# PowerCastel.net
KiCad netlist of a schematic drawn in EAGLE
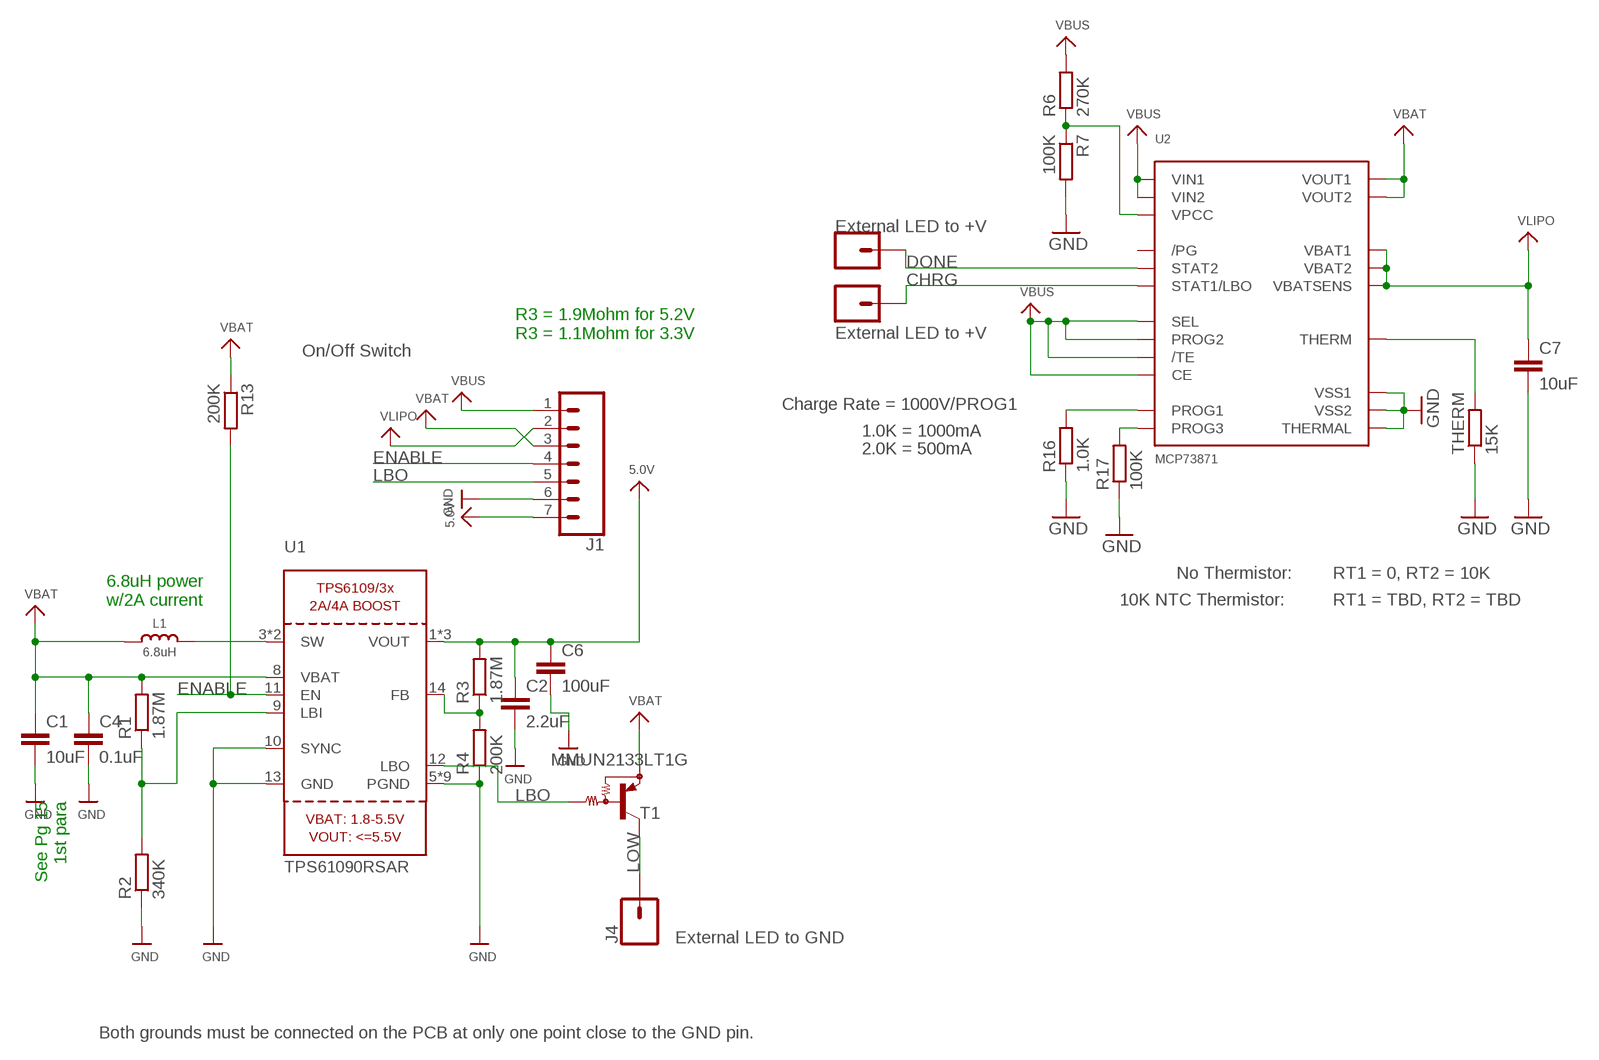
[diagram p0: schematic, sheet 1]

(export (version "E")
  (design (tool "Eeschema 10.0.6"))
  (components
    (comp (ref "C1")
      (value "10uF")
      (footprint "eagle-import:C0603")
      (libsource (lib "eagle-import") (part "C-EUC0603"))
    )
    (comp (ref "C2")
      (value "2.2uF")
      (footprint "eagle-import:C0603")
      (libsource (lib "eagle-import") (part "C-EUC0603"))
    )
    (comp (ref "C4")
      (value "0.1uF")
      (footprint "eagle-import:C0603")
      (libsource (lib "eagle-import") (part "C-EUC0603"))
    )
    (comp (ref "C6")
      (value "100uF")
      (footprint "eagle-import:C0805")
      (libsource (lib "eagle-import") (part "C-EUC0805"))
    )
    (comp (ref "C7")
      (value "10uF")
      (footprint "eagle-import:C0603")
      (libsource (lib "eagle-import") (part "C-EUC0603"))
    )
    (comp (ref "J1")
      (value "CONN_07NO_SILK")
      (footprint "eagle-import:1X07_NO_SILK")
      (libsource (lib "eagle-import") (part "CONN_07NO_SILK"))
    )
    (comp (ref "J2")
      (value "CONN_01PTH_NO_SILK_YES_STOP")
      (footprint "eagle-import:1X01_NO_SILK")
      (libsource (lib "eagle-import") (part "CONN_01PTH_NO_SILK_YES_STOP"))
    )
    (comp (ref "J3")
      (value "CONN_01PTH_NO_SILK_YES_STOP")
      (footprint "eagle-import:1X01_NO_SILK")
      (libsource (lib "eagle-import") (part "CONN_01PTH_NO_SILK_YES_STOP"))
    )
    (comp (ref "J4")
      (value "CONN_01PTH_NO_SILK_YES_STOP")
      (footprint "eagle-import:1X01_NO_SILK")
      (libsource (lib "eagle-import") (part "CONN_01PTH_NO_SILK_YES_STOP"))
    )
    (comp (ref "L1")
      (value "6.8uH")
      (footprint "eagle-import:INDUCTOR_5X5MM_TDK_VLC5045")
      (libsource (lib "eagle-import") (part "INDUCTORTDK_VLC5045"))
    )
    (comp (ref "R1")
      (value "1.87M")
      (footprint "eagle-import:R0603")
      (libsource (lib "eagle-import") (part "R-EU_R0603"))
    )
    (comp (ref "R2")
      (value "340K")
      (footprint "eagle-import:R0603")
      (libsource (lib "eagle-import") (part "R-EU_R0603"))
    )
    (comp (ref "R3")
      (value "1.87M")
      (footprint "eagle-import:R0603")
      (libsource (lib "eagle-import") (part "R-EU_R0603"))
    )
    (comp (ref "R4")
      (value "200K")
      (footprint "eagle-import:R0603")
      (libsource (lib "eagle-import") (part "R-EU_R0603"))
    )
    (comp (ref "R6")
      (value "270K")
      (footprint "eagle-import:R0603")
      (libsource (lib "eagle-import") (part "R-EU_R0603"))
    )
    (comp (ref "R7")
      (value "100K")
      (footprint "eagle-import:R0603")
      (libsource (lib "eagle-import") (part "R-EU_R0603"))
    )
    (comp (ref "R13")
      (value "200K")
      (footprint "eagle-import:R0603")
      (libsource (lib "eagle-import") (part "R-EU_R0603"))
    )
    (comp (ref "R16")
      (value "1.0K")
      (footprint "eagle-import:R0603")
      (libsource (lib "eagle-import") (part "R-EU_R0603"))
    )
    (comp (ref "R17")
      (value "100K")
      (footprint "eagle-import:R0603")
      (libsource (lib "eagle-import") (part "R-EU_R0603"))
    )
    (comp (ref "T1")
      (value "MMUN2133LT1G")
      (footprint "eagle-import:SC59-BEC")
      (libsource (lib "eagle-import") (part "-PNP_DRIVER-SC59-BECMUN2114T1"))
    )
    (comp (ref "THERM")
      (value "15K")
      (footprint "eagle-import:R0603")
      (libsource (lib "eagle-import") (part "R-EU_R0603"))
    )
    (comp (ref "U1")
      (value "TPS61090RSAR")
      (footprint "eagle-import:PVQFN-16")
      (libsource (lib "eagle-import") (part "VREG_TPS6103X"))
    )
    (comp (ref "U2")
      (value "MCP73871")
      (footprint "eagle-import:QFN20_4MM")
      (libsource (lib "eagle-import") (part "MCP73871"))
    )
  )
  (nets
    (net (code "1") (name "/CHRG") (class "Default")
      (node (ref "J3") (pin "1") (pinfunction "1_1") (pintype "passive"))
      (node (ref "U2") (pin "P$8") (pinfunction "STAT1/LBO_P$8") (pintype "bidirectional"))
    )
    (net (code "2") (name "/DONE") (class "Default")
      (node (ref "J2") (pin "1") (pinfunction "1_1") (pintype "passive"))
      (node (ref "U2") (pin "P$7") (pinfunction "STAT2_P$7") (pintype "bidirectional"))
    )
    (net (code "3") (name "/ENABLE") (class "Default")
      (node (ref "J1") (pin "4") (pinfunction "4_4") (pintype "passive"))
      (node (ref "R13") (pin "2") (pinfunction "2_2") (pintype "passive"))
      (node (ref "U1") (pin "11") (pinfunction "EN_11") (pintype "input"))
    )
    (net (code "4") (name "/LBO") (class "Default")
      (node (ref "J1") (pin "5") (pinfunction "5_5") (pintype "passive"))
      (node (ref "T1") (pin "B") (pinfunction "B_B") (pintype "passive"))
      (node (ref "U1") (pin "12") (pinfunction "LBO_12") (pintype "output"))
    )
    (net (code "5") (name "/LOW") (class "Default")
      (node (ref "J4") (pin "1") (pinfunction "1_1") (pintype "passive"))
      (node (ref "T1") (pin "C") (pinfunction "C_C") (pintype "passive"))
    )
    (net (code "6") (name "5.0V") (class "Default")
      (node (ref "C2") (pin "1") (pinfunction "1_1") (pintype "passive"))
      (node (ref "C6") (pin "1") (pinfunction "1_1") (pintype "passive"))
      (node (ref "J1") (pin "7") (pinfunction "7_7") (pintype "passive"))
      (node (ref "R3") (pin "2") (pinfunction "2_2") (pintype "passive"))
      (node (ref "U1") (pin "1") (pinfunction "VOUT_1") (pintype "power_in"))
      (node (ref "U1") (pin "15") (pinfunction "VOUT_15") (pintype "power_in"))
      (node (ref "U1") (pin "16") (pinfunction "VOUT_16") (pintype "power_in"))
    )
    (net (code "7") (name "GND") (class "Default")
      (node (ref "C1") (pin "2") (pinfunction "2_2") (pintype "passive"))
      (node (ref "C2") (pin "2") (pinfunction "2_2") (pintype "passive"))
      (node (ref "C4") (pin "2") (pinfunction "2_2") (pintype "passive"))
      (node (ref "C6") (pin "2") (pinfunction "2_2") (pintype "passive"))
      (node (ref "C7") (pin "2") (pinfunction "2_2") (pintype "passive"))
      (node (ref "J1") (pin "6") (pinfunction "6_6") (pintype "passive"))
      (node (ref "R16") (pin "1") (pinfunction "1_1") (pintype "passive"))
      (node (ref "R17") (pin "1") (pinfunction "1_1") (pintype "passive"))
      (node (ref "R2") (pin "1") (pinfunction "1_1") (pintype "passive"))
      (node (ref "R4") (pin "1") (pinfunction "1_1") (pintype "passive"))
      (node (ref "R7") (pin "2") (pinfunction "2_2") (pintype "passive"))
      (node (ref "THERM") (pin "1") (pinfunction "1_1") (pintype "passive"))
      (node (ref "U1") (pin "10") (pinfunction "SYNC_10") (pintype "input"))
      (node (ref "U1") (pin "13") (pinfunction "GND_13") (pintype "power_in"))
      (node (ref "U1") (pin "5") (pinfunction "PGND_5") (pintype "power_in"))
      (node (ref "U1") (pin "6") (pinfunction "PGND_6") (pintype "power_in"))
      (node (ref "U1") (pin "7") (pinfunction "PGND_7") (pintype "power_in"))
      (node (ref "U1") (pin "P$18") (pinfunction "PGND_P$18") (pintype "power_in"))
      (node (ref "U1") (pin "P$19") (pinfunction "PGND_P$19") (pintype "power_in"))
      (node (ref "U1") (pin "P$20") (pinfunction "PGND_P$20") (pintype "power_in"))
      (node (ref "U1") (pin "P$21") (pinfunction "PGND_P$21") (pintype "power_in"))
      (node (ref "U1") (pin "P$22") (pinfunction "PGND_P$22") (pintype "power_in"))
      (node (ref "U1") (pin "THERMAL") (pinfunction "PGND_THERMAL") (pintype "power_in"))
      (node (ref "U2") (pin "P$10") (pinfunction "VSS1_P$10") (pintype "bidirectional"))
      (node (ref "U2") (pin "P$11") (pinfunction "VSS2_P$11") (pintype "bidirectional"))
      (node (ref "U2") (pin "P$21") (pinfunction "THERMAL_P$21") (pintype "bidirectional"))
    )
    (net (code "8") (name "Net-(L1-2)") (class "Default")
      (node (ref "L1") (pin "P$2") (pinfunction "2_P$2") (pintype "passive"))
      (node (ref "U1") (pin "3") (pinfunction "SW_3") (pintype "input"))
      (node (ref "U1") (pin "4") (pinfunction "SW_4") (pintype "input"))
    )
    (net (code "9") (name "Net-(U1-FB)") (class "Default")
      (node (ref "R3") (pin "1") (pinfunction "1_1") (pintype "passive"))
      (node (ref "R4") (pin "2") (pinfunction "2_2") (pintype "passive"))
      (node (ref "U1") (pin "14") (pinfunction "FB_14") (pintype "input"))
    )
    (net (code "10") (name "Net-(U1-LBI)") (class "Default")
      (node (ref "R1") (pin "1") (pinfunction "1_1") (pintype "passive"))
      (node (ref "R2") (pin "2") (pinfunction "2_2") (pintype "passive"))
      (node (ref "U1") (pin "9") (pinfunction "LBI_9") (pintype "input"))
    )
    (net (code "11") (name "Net-(U2-PROG1)") (class "Default")
      (node (ref "R16") (pin "2") (pinfunction "2_2") (pintype "passive"))
      (node (ref "U2") (pin "P$13") (pinfunction "PROG1_P$13") (pintype "bidirectional"))
    )
    (net (code "12") (name "Net-(U2-PROG3)") (class "Default")
      (node (ref "R17") (pin "2") (pinfunction "2_2") (pintype "passive"))
      (node (ref "U2") (pin "P$12") (pinfunction "PROG3_P$12") (pintype "bidirectional"))
    )
    (net (code "13") (name "Net-(U2-THERM)") (class "Default")
      (node (ref "THERM") (pin "2") (pinfunction "2_2") (pintype "passive"))
      (node (ref "U2") (pin "P$5") (pinfunction "THERM_P$5") (pintype "bidirectional"))
    )
    (net (code "14") (name "Net-(U2-VPCC)") (class "Default")
      (node (ref "R6") (pin "1") (pinfunction "1_1") (pintype "passive"))
      (node (ref "R7") (pin "1") (pinfunction "1_1") (pintype "passive"))
      (node (ref "U2") (pin "P$2") (pinfunction "VPCC_P$2") (pintype "bidirectional"))
    )
    (net (code "15") (name "VBAT") (class "Default")
      (node (ref "C1") (pin "1") (pinfunction "1_1") (pintype "passive"))
      (node (ref "C4") (pin "1") (pinfunction "1_1") (pintype "passive"))
      (node (ref "J1") (pin "3") (pinfunction "3_3") (pintype "passive"))
      (node (ref "L1") (pin "P$1") (pinfunction "1_P$1") (pintype "passive"))
      (node (ref "R1") (pin "2") (pinfunction "2_2") (pintype "passive"))
      (node (ref "R13") (pin "1") (pinfunction "1_1") (pintype "passive"))
      (node (ref "T1") (pin "E") (pinfunction "E_E") (pintype "passive"))
      (node (ref "U1") (pin "8") (pinfunction "VBAT_8") (pintype "input"))
      (node (ref "U2") (pin "P$1") (pinfunction "VOUT1_P$1") (pintype "bidirectional"))
      (node (ref "U2") (pin "P$20") (pinfunction "VOUT2_P$20") (pintype "bidirectional"))
    )
    (net (code "16") (name "VBUS") (class "Default")
      (node (ref "J1") (pin "1") (pinfunction "1_1") (pintype "passive"))
      (node (ref "R6") (pin "2") (pinfunction "2_2") (pintype "passive"))
      (node (ref "U2") (pin "P$17") (pinfunction "CE_P$17") (pintype "bidirectional"))
      (node (ref "U2") (pin "P$18") (pinfunction "VIN1_P$18") (pintype "bidirectional"))
      (node (ref "U2") (pin "P$19") (pinfunction "VIN2_P$19") (pintype "bidirectional"))
      (node (ref "U2") (pin "P$3") (pinfunction "SEL_P$3") (pintype "bidirectional"))
      (node (ref "U2") (pin "P$4") (pinfunction "PROG2_P$4") (pintype "bidirectional"))
      (node (ref "U2") (pin "P$9") (pinfunction "/TE_P$9") (pintype "bidirectional"))
    )
    (net (code "17") (name "VLIPO") (class "Default")
      (node (ref "C7") (pin "1") (pinfunction "1_1") (pintype "passive"))
      (node (ref "J1") (pin "2") (pinfunction "2_2") (pintype "passive"))
      (node (ref "U2") (pin "P$14") (pinfunction "VBAT1_P$14") (pintype "bidirectional"))
      (node (ref "U2") (pin "P$15") (pinfunction "VBAT2_P$15") (pintype "bidirectional"))
      (node (ref "U2") (pin "P$16") (pinfunction "VBATSENS_P$16") (pintype "bidirectional"))
    )
    (net (code "18") (name "unconnected-(U2-{slash}PG-PadP$6)") (class "Default")
      (node (ref "U2") (pin "P$6") (pinfunction "/PG_P$6") (pintype "bidirectional"))
    )
  )
)
